# photoFrame.net
KiCad netlist of a schematic drawn in EAGLE
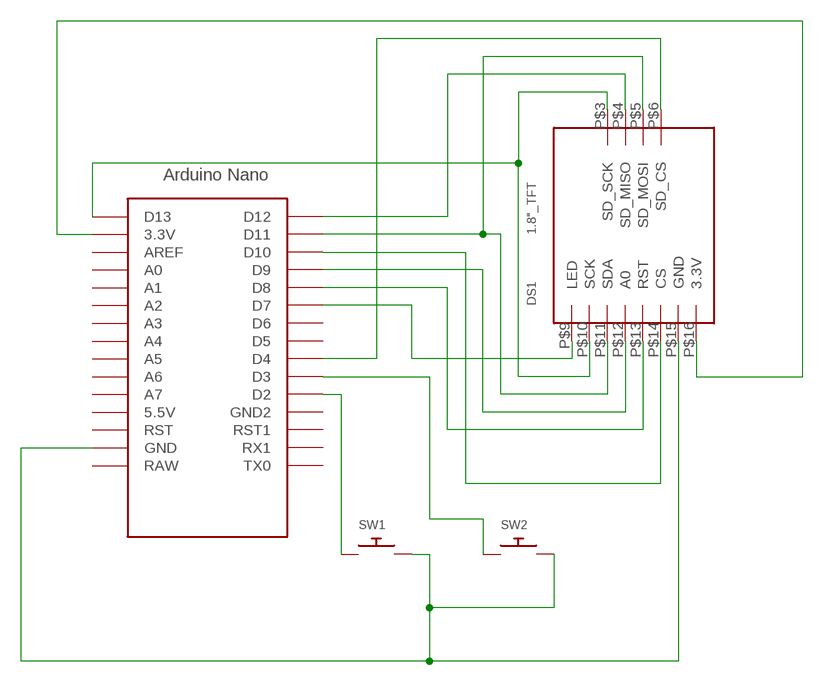
[diagram p0: schematic, sheet 1]

(export (version "E")
  (design (tool "Eeschema 10.0.6"))
  (components
    (comp (ref "DS1")
      (value "1.8\"_TFT")
      (footprint "eagle-import:1.8__TFT")
      (libsource (lib "eagle-import") (part "1.8{dblquote}_TFT"))
    )
    (comp (ref "SW1")
      (value "SWITCH_PUSHBUTTONC&K_KSS")
      (footprint "eagle-import:BTN_CK_KSS")
      (libsource (lib "eagle-import") (part "SWITCH_PUSHBUTTONC&K_KSS"))
    )
    (comp (ref "SW2")
      (value "SWITCH_PUSHBUTTONC&K_KSS")
      (footprint "eagle-import:BTN_CK_KSS")
      (libsource (lib "eagle-import") (part "SWITCH_PUSHBUTTONC&K_KSS"))
    )
    (comp (ref "U1")
      (value "NANO")
      (footprint "eagle-import:NANO")
      (libsource (lib "eagle-import") (part "NANO"))
    )
  )
  (nets
    (net (code "1") (name "Net-(DS1-3.3V)") (class "Default")
      (node (ref "DS1") (pin "P$16") (pinfunction "3.3V_P$16") (pintype "bidirectional"))
      (node (ref "U1") (pin "3.3V") (pinfunction "3.3V_3.3V") (pintype "bidirectional"))
    )
    (net (code "2") (name "Net-(DS1-A0)") (class "Default")
      (node (ref "DS1") (pin "P$12") (pinfunction "A0_P$12") (pintype "bidirectional"))
      (node (ref "U1") (pin "D9") (pinfunction "D9_D9") (pintype "bidirectional"))
    )
    (net (code "3") (name "Net-(DS1-CS)") (class "Default")
      (node (ref "DS1") (pin "P$14") (pinfunction "CS_P$14") (pintype "bidirectional"))
      (node (ref "U1") (pin "D10") (pinfunction "D10_D10") (pintype "bidirectional"))
    )
    (net (code "4") (name "Net-(DS1-GND)") (class "Default")
      (node (ref "DS1") (pin "P$15") (pinfunction "GND_P$15") (pintype "bidirectional"))
      (node (ref "SW1") (pin "P$2") (pinfunction "P$2_P$2") (pintype "passive"))
      (node (ref "SW2") (pin "P$2") (pinfunction "P$2_P$2") (pintype "passive"))
      (node (ref "U1") (pin "GND") (pinfunction "GND_GND") (pintype "bidirectional"))
    )
    (net (code "5") (name "Net-(DS1-LED)") (class "Default")
      (node (ref "DS1") (pin "P$9") (pinfunction "LED_P$9") (pintype "bidirectional"))
      (node (ref "U1") (pin "D7") (pinfunction "D7_D7") (pintype "bidirectional"))
    )
    (net (code "6") (name "Net-(DS1-RST)") (class "Default")
      (node (ref "DS1") (pin "P$13") (pinfunction "RST_P$13") (pintype "bidirectional"))
      (node (ref "U1") (pin "D8") (pinfunction "D8_D8") (pintype "bidirectional"))
    )
    (net (code "7") (name "Net-(DS1-SCK)") (class "Default")
      (node (ref "DS1") (pin "P$10") (pinfunction "SCK_P$10") (pintype "bidirectional"))
      (node (ref "DS1") (pin "P$3") (pinfunction "SD_SCK_P$3") (pintype "bidirectional"))
      (node (ref "U1") (pin "D13") (pinfunction "D13_D13") (pintype "bidirectional"))
    )
    (net (code "8") (name "Net-(DS1-SDA)") (class "Default")
      (node (ref "DS1") (pin "P$11") (pinfunction "SDA_P$11") (pintype "bidirectional"))
      (node (ref "DS1") (pin "P$5") (pinfunction "SD_MOSI_P$5") (pintype "bidirectional"))
      (node (ref "U1") (pin "D11") (pinfunction "D11_D11") (pintype "bidirectional"))
    )
    (net (code "9") (name "Net-(DS1-SD_CS)") (class "Default")
      (node (ref "DS1") (pin "P$6") (pinfunction "SD_CS_P$6") (pintype "bidirectional"))
      (node (ref "U1") (pin "D4") (pinfunction "D4_D4") (pintype "bidirectional"))
    )
    (net (code "10") (name "Net-(DS1-SD_MISO)") (class "Default")
      (node (ref "DS1") (pin "P$4") (pinfunction "SD_MISO_P$4") (pintype "bidirectional"))
      (node (ref "U1") (pin "D12") (pinfunction "D12_D12") (pintype "bidirectional"))
    )
    (net (code "11") (name "Net-(SW1-PadP$1)") (class "Default")
      (node (ref "SW1") (pin "P$1") (pinfunction "P$1_P$1") (pintype "passive"))
      (node (ref "U1") (pin "D2") (pinfunction "D2_D2") (pintype "bidirectional"))
    )
    (net (code "12") (name "Net-(SW2-PadP$1)") (class "Default")
      (node (ref "SW2") (pin "P$1") (pinfunction "P$1_P$1") (pintype "passive"))
      (node (ref "U1") (pin "D3") (pinfunction "D3_D3") (pintype "bidirectional"))
    )
    (net (code "13") (name "unconnected-(U1-5.5V-Pad5V)") (class "Default")
      (node (ref "U1") (pin "5V") (pinfunction "5.5V_5V") (pintype "bidirectional"))
    )
    (net (code "14") (name "unconnected-(U1-GND2-PadGND1)") (class "Default")
      (node (ref "U1") (pin "GND1") (pinfunction "GND2_GND1") (pintype "bidirectional"))
    )
    (net (code "15") (name "unconnected-(U1-PadA0)") (class "Default")
      (node (ref "U1") (pin "A0") (pinfunction "A0_A0") (pintype "bidirectional"))
    )
    (net (code "16") (name "unconnected-(U1-PadA1)") (class "Default")
      (node (ref "U1") (pin "A1") (pinfunction "A1_A1") (pintype "bidirectional"))
    )
    (net (code "17") (name "unconnected-(U1-PadA2)") (class "Default")
      (node (ref "U1") (pin "A2") (pinfunction "A2_A2") (pintype "bidirectional"))
    )
    (net (code "18") (name "unconnected-(U1-PadA3)") (class "Default")
      (node (ref "U1") (pin "A3") (pinfunction "A3_A3") (pintype "bidirectional"))
    )
    (net (code "19") (name "unconnected-(U1-PadA4)") (class "Default")
      (node (ref "U1") (pin "A4") (pinfunction "A4_A4") (pintype "bidirectional"))
    )
    (net (code "20") (name "unconnected-(U1-PadA5)") (class "Default")
      (node (ref "U1") (pin "A5") (pinfunction "A5_A5") (pintype "bidirectional"))
    )
    (net (code "21") (name "unconnected-(U1-PadA6)") (class "Default")
      (node (ref "U1") (pin "A6") (pinfunction "A6_A6") (pintype "bidirectional"))
    )
    (net (code "22") (name "unconnected-(U1-PadA7)") (class "Default")
      (node (ref "U1") (pin "A7") (pinfunction "A7_A7") (pintype "bidirectional"))
    )
    (net (code "23") (name "unconnected-(U1-PadAREF)") (class "Default")
      (node (ref "U1") (pin "AREF") (pinfunction "AREF_AREF") (pintype "bidirectional"))
    )
    (net (code "24") (name "unconnected-(U1-PadD5)") (class "Default")
      (node (ref "U1") (pin "D5") (pinfunction "D5_D5") (pintype "bidirectional"))
    )
    (net (code "25") (name "unconnected-(U1-PadD6)") (class "Default")
      (node (ref "U1") (pin "D6") (pinfunction "D6_D6") (pintype "bidirectional"))
    )
    (net (code "26") (name "unconnected-(U1-PadICSP1)") (class "Default")
      (node (ref "U1") (pin "ICSP1") (pinfunction "ICSP1_ICSP1") (pintype "bidirectional"))
    )
    (net (code "27") (name "unconnected-(U1-PadICSP2)") (class "Default")
      (node (ref "U1") (pin "ICSP2") (pinfunction "ICSP2_ICSP2") (pintype "bidirectional"))
    )
    (net (code "28") (name "unconnected-(U1-PadICSP3)") (class "Default")
      (node (ref "U1") (pin "ICSP3") (pinfunction "ICSP3_ICSP3") (pintype "bidirectional"))
    )
    (net (code "29") (name "unconnected-(U1-PadICSP4)") (class "Default")
      (node (ref "U1") (pin "ICSP4") (pinfunction "ICSP4_ICSP4") (pintype "bidirectional"))
    )
    (net (code "30") (name "unconnected-(U1-PadICSP5)") (class "Default")
      (node (ref "U1") (pin "ICSP5") (pinfunction "ICSP5_ICSP5") (pintype "bidirectional"))
    )
    (net (code "31") (name "unconnected-(U1-PadICSP6)") (class "Default")
      (node (ref "U1") (pin "ICSP6") (pinfunction "ICSP6_ICSP6") (pintype "bidirectional"))
    )
    (net (code "32") (name "unconnected-(U1-PadRAW)") (class "Default")
      (node (ref "U1") (pin "RAW") (pinfunction "RAW_RAW") (pintype "bidirectional"))
    )
    (net (code "33") (name "unconnected-(U1-PadRST)") (class "Default")
      (node (ref "U1") (pin "RST") (pinfunction "RST_RST") (pintype "bidirectional"))
    )
    (net (code "34") (name "unconnected-(U1-PadRST1)") (class "Default")
      (node (ref "U1") (pin "RST1") (pinfunction "RST1_RST1") (pintype "bidirectional"))
    )
    (net (code "35") (name "unconnected-(U1-PadRX1)") (class "Default")
      (node (ref "U1") (pin "RX1") (pinfunction "RX1_RX1") (pintype "bidirectional"))
    )
    (net (code "36") (name "unconnected-(U1-PadTX0)") (class "Default")
      (node (ref "U1") (pin "TX0") (pinfunction "TX0_TX0") (pintype "bidirectional"))
    )
  )
)
